# CAN_bus.net
KiCad netlist of a schematic drawn in Altium Designer
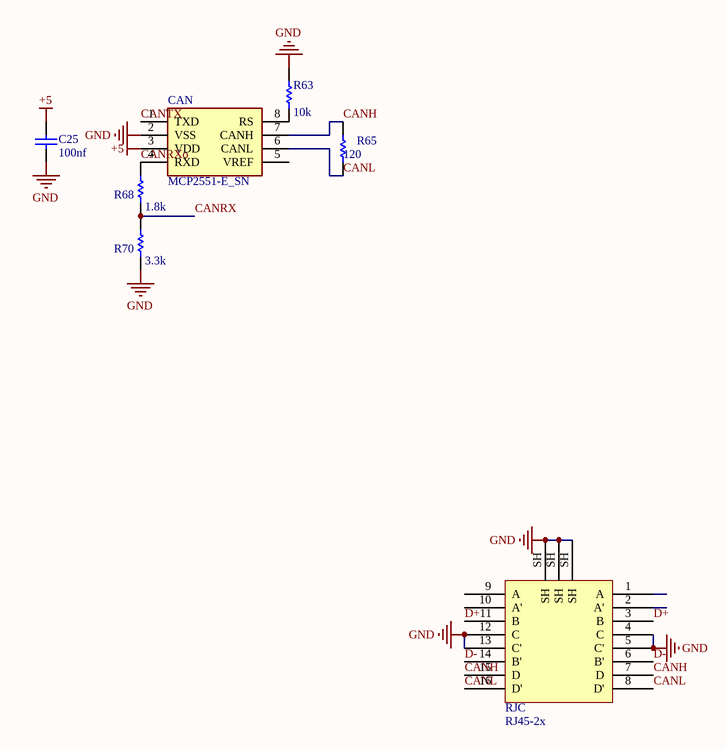
[diagram p0: CAN bus.SchDoc]

(export (version "E")
  (design (tool "Eeschema 10.0.6"))
  (components
    (comp (ref "C25")
      (value "100nf")
      (footprint "0805")
      (description "Capacitor")
      (fields (field (name "PUBLISHER") "Altium Limited"))
      (libsource (lib "Miscellaneous Devices") (part "Cap"))
    )
    (comp (ref "CAN")
      (value "MCP2551-E_SN")
      (footprint "SamacSys:SOIC127P600X175-8N")
      (description "Integrated Circuit")
      (fields
        (field (name "MANUFACTURER_PART_NUMBER") "MCP2551-E/SN")
        (field (name "MOUSER PART NUMBER") "579-MCP2551-E/SN")
      )
      (libsource (lib "*") (part "MCP2551-E_SN"))
    )
    (comp (ref "R63")
      (value "10k")
      (footprint "0805")
      (description "Semiconductor Resistor")
      (fields (field (name "PUBLISHER") "Altium Limited"))
      (libsource (lib "KN2CLib") (part "Res"))
    )
    (comp (ref "R65")
      (value "120")
      (footprint "0805")
      (description "Semiconductor Resistor")
      (fields (field (name "PUBLISHER") "Altium Limited"))
      (libsource (lib "KN2CLib") (part "Res"))
    )
    (comp (ref "R68")
      (value "1.8k")
      (footprint "0805")
      (description "Semiconductor Resistor")
      (fields (field (name "PUBLISHER") "Altium Limited"))
      (libsource (lib "KN2CLib") (part "Res"))
    )
    (comp (ref "R70")
      (value "3.3k")
      (footprint "0805")
      (description "Semiconductor Resistor")
      (fields (field (name "PUBLISHER") "Altium Limited"))
      (libsource (lib "KN2CLib") (part "Res"))
    )
    (comp (ref "RJC")
      (value "RJ45-2x")
      (footprint "RJ45_dual_right")
      (description "RJ45_Dual-Right")
      (libsource (lib "aqda") (part "RJ45_dual_right"))
    )
  )
  (nets
    (net (code "1") (name "+5") (class "Default")
      (node (ref "C25") (pin "2") (pinfunction "2_2") (pintype "passive"))
      (node (ref "CAN") (pin "3") (pinfunction "VDD_3") (pintype "passive"))
    )
    (net (code "2") (name "/CANH") (class "Default")
      (node (ref "CAN") (pin "7") (pinfunction "CANH_7") (pintype "passive"))
      (node (ref "R65") (pin "1") (pinfunction "1_1") (pintype "passive"))
      (node (ref "RJC") (pin "15") (pinfunction "D_15") (pintype "passive"))
      (node (ref "RJC") (pin "7") (pinfunction "D_7") (pintype "passive"))
    )
    (net (code "3") (name "/CANL") (class "Default")
      (node (ref "CAN") (pin "6") (pinfunction "CANL_6") (pintype "passive"))
      (node (ref "R65") (pin "2") (pinfunction "2_2") (pintype "passive"))
      (node (ref "RJC") (pin "16") (pinfunction "D'_16") (pintype "passive"))
      (node (ref "RJC") (pin "8") (pinfunction "D'_8") (pintype "passive"))
    )
    (net (code "4") (name "/CANRX") (class "Default")
      (node (ref "R68") (pin "2") (pinfunction "2_2") (pintype "passive"))
      (node (ref "R70") (pin "1") (pinfunction "1_1") (pintype "passive"))
    )
    (net (code "5") (name "/CANRXo") (class "Default")
      (node (ref "CAN") (pin "4") (pinfunction "RXD_4") (pintype "passive"))
      (node (ref "R68") (pin "1") (pinfunction "1_1") (pintype "passive"))
    )
    (net (code "6") (name "/CANTX") (class "Default")
      (node (ref "CAN") (pin "1") (pinfunction "TXD_1") (pintype "passive"))
    )
    (net (code "7") (name "/D+") (class "Default")
      (node (ref "RJC") (pin "11") (pinfunction "B_11") (pintype "passive"))
      (node (ref "RJC") (pin "3") (pinfunction "B_3") (pintype "passive"))
    )
    (net (code "8") (name "/D-") (class "Default")
      (node (ref "RJC") (pin "14") (pinfunction "B'_14") (pintype "passive"))
      (node (ref "RJC") (pin "6") (pinfunction "B'_6") (pintype "passive"))
    )
    (net (code "9") (name "GND") (class "Default")
      (node (ref "C25") (pin "1") (pinfunction "1_1") (pintype "passive"))
      (node (ref "CAN") (pin "2") (pinfunction "VSS_2") (pintype "passive"))
      (node (ref "R63") (pin "1") (pinfunction "1_1") (pintype "passive"))
      (node (ref "R70") (pin "2") (pinfunction "2_2") (pintype "passive"))
      (node (ref "RJC") (pin "12") (pinfunction "C_12") (pintype "passive"))
      (node (ref "RJC") (pin "13") (pinfunction "C'_13") (pintype "passive"))
      (node (ref "RJC") (pin "4") (pinfunction "C_4") (pintype "passive"))
      (node (ref "RJC") (pin "5") (pinfunction "C'_5") (pintype "passive"))
      (node (ref "RJC") (pin "SH") (pinfunction "SH_SH") (pintype "passive"))
    )
    (net (code "10") (name "Net-(CAN-RS)") (class "Default")
      (node (ref "CAN") (pin "8") (pinfunction "RS_8") (pintype "passive"))
      (node (ref "R63") (pin "2") (pinfunction "2_2") (pintype "passive"))
    )
    (net (code "11") (name "unconnected-(CAN-VREF-Pad5)") (class "Default")
      (node (ref "CAN") (pin "5") (pinfunction "VREF_5") (pintype "passive"))
    )
    (net (code "12") (name "unconnected-(RJC-A'-Pad2)") (class "Default")
      (node (ref "RJC") (pin "2") (pinfunction "A'_2") (pintype "passive"))
    )
    (net (code "13") (name "unconnected-(RJC-A'-Pad10)") (class "Default")
      (node (ref "RJC") (pin "10") (pinfunction "A'_10") (pintype "passive"))
    )
    (net (code "14") (name "unconnected-(RJC-A-Pad1)") (class "Default")
      (node (ref "RJC") (pin "1") (pinfunction "A_1") (pintype "passive"))
    )
    (net (code "15") (name "unconnected-(RJC-A-Pad9)") (class "Default")
      (node (ref "RJC") (pin "9") (pinfunction "A_9") (pintype "passive"))
    )
  )
)
